# 4_DAC.net
KiCad netlist of a schematic drawn in Altium Designer
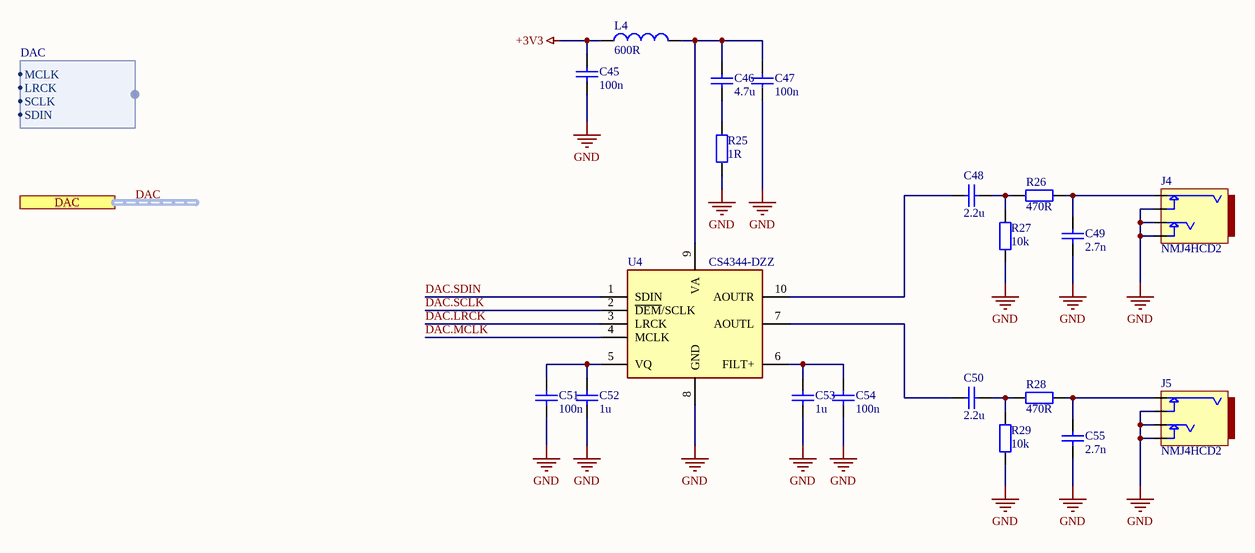
[diagram p0: [4] DAC.SchDoc]

(export (version "E")
  (design (tool "Eeschema 10.0.6"))
  (components
    (comp (ref "C45")
      (value "100n")
      (footprint "STguitar:Capacitor 0603")
      (description "Multilayer Ceramic Capacitors MLCC - SMD/SMT 0603 16VDC 0.1uF 10% X7R")
      (fields
        (field (name "MANUFACTURER PART NUMBER") "EMK107B7104KA-T")
        (field (name "MANUFACTURER") "Taiyo Yuden")
      )
      (libsource (lib "STguitar") (part "Capacitor 100n 10% 0603 EMK107B7104KA-T"))
    )
    (comp (ref "C46")
      (value "4.7u")
      (footprint "STguitar:Capacitor 0603")
      (description "Multilayer Ceramic Capacitors MLCC - SMD/SMT 0603 16VDC 4.7uF 10% X5R")
      (fields
        (field (name "MANUFACTURER PART NUMBER") "EMK107ABJ475KA-T")
        (field (name "MANUFACTURER") "Taiyo Yuden")
      )
      (libsource (lib "STguitar") (part "Capacitor 4.7u 10% 0603 EMK107ABJ475KA-T"))
    )
    (comp (ref "C47")
      (value "100n")
      (footprint "STguitar:Capacitor 0603")
      (description "Multilayer Ceramic Capacitors MLCC - SMD/SMT 0603 16VDC 0.1uF 10% X7R")
      (fields
        (field (name "MANUFACTURER PART NUMBER") "EMK107B7104KA-T")
        (field (name "MANUFACTURER") "Taiyo Yuden")
      )
      (libsource (lib "STguitar") (part "Capacitor 100n 10% 0603 EMK107B7104KA-T"))
    )
    (comp (ref "C48")
      (value "2.2u")
      (footprint "STguitar:Capacitor 0603")
      (description "Multilayer Ceramic Capacitors MLCC - SMD/SMT 0603 16VDC 2.2uF 10% X5R")
      (fields
        (field (name "MANUFACTURER PART NUMBER") "EMK107BJ225KA-T")
        (field (name "MANUFACTURER") "Taiyo Yuden")
      )
      (libsource (lib "STguitar") (part "Capacitor 2.2u 10% 0603 EMK107BJ225KA-T"))
    )
    (comp (ref "C49")
      (value "2.7n")
      (footprint "STguitar:Capacitor 0603")
      (description "Multilayer Ceramic Capacitors MLCC - SMD/SMT 0603 50VDC 2.7nF 10% Low Distort")
      (fields
        (field (name "MANUFACTURER PART NUMBER") "UMK107SD272KA-T")
        (field (name "MANUFACTURER") "Taiyo Yuden")
      )
      (libsource (lib "STguitar") (part "Capacitor 2.7n 10% 0603 UMK107SD272KA-T"))
    )
    (comp (ref "C50")
      (value "2.2u")
      (footprint "STguitar:Capacitor 0603")
      (description "Multilayer Ceramic Capacitors MLCC - SMD/SMT 0603 16VDC 2.2uF 10% X5R")
      (fields
        (field (name "MANUFACTURER PART NUMBER") "EMK107BJ225KA-T")
        (field (name "MANUFACTURER") "Taiyo Yuden")
      )
      (libsource (lib "STguitar") (part "Capacitor 2.2u 10% 0603 EMK107BJ225KA-T"))
    )
    (comp (ref "C51")
      (value "100n")
      (footprint "STguitar:Capacitor 0603")
      (description "Multilayer Ceramic Capacitors MLCC - SMD/SMT 0603 16VDC 0.1uF 10% X7R")
      (fields
        (field (name "MANUFACTURER PART NUMBER") "EMK107B7104KA-T")
        (field (name "MANUFACTURER") "Taiyo Yuden")
      )
      (libsource (lib "STguitar") (part "Capacitor 100n 10% 0603 EMK107B7104KA-T"))
    )
    (comp (ref "C52")
      (value "1u")
      (footprint "STguitar:Capacitor 0603")
      (description "Multilayer Ceramic Capacitors MLCC - SMD/SMT 0603 16VDC 1uF 10% X7R")
      (fields
        (field (name "MANUFACTURER PART NUMBER") "EMK107B7105KA-T")
        (field (name "MANUFACTURER") "Taiyo Yuden")
      )
      (libsource (lib "STguitar") (part "Capacitor 1u 10% 0603 EMK107B7105KA-T"))
    )
    (comp (ref "C53")
      (value "1u")
      (footprint "STguitar:Capacitor 0603")
      (description "Multilayer Ceramic Capacitors MLCC - SMD/SMT 0603 16VDC 1uF 10% X7R")
      (fields
        (field (name "MANUFACTURER PART NUMBER") "EMK107B7105KA-T")
        (field (name "MANUFACTURER") "Taiyo Yuden")
      )
      (libsource (lib "STguitar") (part "Capacitor 1u 10% 0603 EMK107B7105KA-T"))
    )
    (comp (ref "C54")
      (value "100n")
      (footprint "STguitar:Capacitor 0603")
      (description "Multilayer Ceramic Capacitors MLCC - SMD/SMT 0603 16VDC 0.1uF 10% X7R")
      (fields
        (field (name "MANUFACTURER PART NUMBER") "EMK107B7104KA-T")
        (field (name "MANUFACTURER") "Taiyo Yuden")
      )
      (libsource (lib "STguitar") (part "Capacitor 100n 10% 0603 EMK107B7104KA-T"))
    )
    (comp (ref "C55")
      (value "2.7n")
      (footprint "STguitar:Capacitor 0603")
      (description "Multilayer Ceramic Capacitors MLCC - SMD/SMT 0603 50VDC 2.7nF 10% Low Distort")
      (fields
        (field (name "MANUFACTURER PART NUMBER") "UMK107SD272KA-T")
        (field (name "MANUFACTURER") "Taiyo Yuden")
      )
      (libsource (lib "STguitar") (part "Capacitor 2.7n 10% 0603 UMK107SD272KA-T"))
    )
    (comp (ref "J4")
      (value "NMJ4HCD2")
      (footprint "STguitar:Mechanical NMJ4HCD2")
      (description "Phone Connectors 2C MONO 2-SPST NC")
      (fields (field (name "MANUFACTURER") "Neutrik"))
      (libsource (lib "STguitar") (part "Mechanical JACK Phone Connectors 2C MONO 2-SPST NC"))
    )
    (comp (ref "J5")
      (value "NMJ4HCD2")
      (footprint "STguitar:Mechanical NMJ4HCD2")
      (description "Phone Connectors 2C MONO 2-SPST NC")
      (fields (field (name "MANUFACTURER") "Neutrik"))
      (libsource (lib "STguitar") (part "Mechanical JACK Phone Connectors 2C MONO 2-SPST NC"))
    )
    (comp (ref "L4")
      (value "600R")
      (footprint "STguitar:Inductor 0603")
      (description "Ferrite Beads 600ohms 100MHz 300mA Monolithic 0603 SMD")
      (fields
        (field (name "MANUFACTURER PART NUMBER") "HZ0603C601R-10")
        (field (name "MANUFACTURER") "Laird Performance Materials")
      )
      (libsource (lib "STguitar") (part "Inductor 600R 1% 0603 HZ0603C601R-10"))
    )
    (comp (ref "R25")
      (value "1R")
      (footprint "STguitar:Resistor 0603")
      (description "Thin Film Resistors - SMD 1/10W 1 ohm ohm 50 ppm")
      (fields
        (field (name "MANUFACTURER PART NUMBER") "RT0603FRE071RL")
        (field (name "MANUFACTURER") "Yageo")
      )
      (libsource (lib "STguitar") (part "Resistor 1R 1% 0603 RT0603FRE071RL"))
    )
    (comp (ref "R26")
      (value "470R")
      (footprint "STguitar:Resistor 0603")
      (description "Thin Film Resistors - SMD 1/10W 470 ohm 1% 50ppm")
      (fields
        (field (name "MANUFACTURER PART NUMBER") "RT0603FRE07470RL")
        (field (name "MANUFACTURER") "Yageo")
      )
      (libsource (lib "STguitar") (part "Resistor 470R 1% 0603 RT0603FRE07470RL"))
    )
    (comp (ref "R27")
      (value "10k")
      (footprint "STguitar:Resistor 0603")
      (description "Thin Film Resistors - SMD 10K ohm 1% 1/10W")
      (fields
        (field (name "MANUFACTURER PART NUMBER") "RT0603FRE0710KL")
        (field (name "MANUFACTURER") "Yageo")
      )
      (libsource (lib "STguitar") (part "Resistor 10k 1% 0603 RT0603FRE0710KL"))
    )
    (comp (ref "R28")
      (value "470R")
      (footprint "STguitar:Resistor 0603")
      (description "Thin Film Resistors - SMD 1/10W 470 ohm 1% 50ppm")
      (fields
        (field (name "MANUFACTURER PART NUMBER") "RT0603FRE07470RL")
        (field (name "MANUFACTURER") "Yageo")
      )
      (libsource (lib "STguitar") (part "Resistor 470R 1% 0603 RT0603FRE07470RL"))
    )
    (comp (ref "R29")
      (value "10k")
      (footprint "STguitar:Resistor 0603")
      (description "Thin Film Resistors - SMD 10K ohm 1% 1/10W")
      (fields
        (field (name "MANUFACTURER PART NUMBER") "RT0603FRE0710KL")
        (field (name "MANUFACTURER") "Yageo")
      )
      (libsource (lib "STguitar") (part "Resistor 10k 1% 0603 RT0603FRE0710KL"))
    )
    (comp (ref "U4")
      (value "CS4344-DZZ")
      (footprint "STguitar:TSSOP10")
      (description "Audio D/A Converter ICs Stereo DAC 24-Bit 192kHz")
      (fields (field (name "MANUFACTURER") "Cirrus Logic"))
      (libsource (lib "STguitar") (part "IC Audio D/A Converter ICs Stereo DAC 24-Bit 192kHz CS4344-DZZ"))
    )
  )
  (nets
    (net (code "2") (name "+3V3") (class "Default")
      (node (ref "C45") (pin "2") (pinfunction "2_2") (pintype "passive"))
      (node (ref "L4") (pin "1") (pinfunction "1_1") (pintype "passive"))
    )
    (net (code "3") (name "/DAC.LRCK") (class "Default")
      (node (ref "U4") (pin "3") (pinfunction "LRCK_3") (pintype "passive"))
    )
    (net (code "4") (name "/DAC.MCLK") (class "Default")
      (node (ref "U4") (pin "4") (pinfunction "MCLK_4") (pintype "passive"))
    )
    (net (code "5") (name "/DAC.SCLK") (class "Default")
      (node (ref "U4") (pin "2") (pinfunction "~{DEM}/SCLK_2") (pintype "passive"))
    )
    (net (code "6") (name "/DAC.SDIN") (class "Default")
      (node (ref "U4") (pin "1") (pinfunction "SDIN_1") (pintype "passive"))
    )
    (net (code "8") (name "GND") (class "Default")
      (node (ref "C45") (pin "1") (pinfunction "1_1") (pintype "passive"))
      (node (ref "C47") (pin "1") (pinfunction "1_1") (pintype "passive"))
      (node (ref "C49") (pin "1") (pinfunction "1_1") (pintype "passive"))
      (node (ref "C51") (pin "1") (pinfunction "1_1") (pintype "passive"))
      (node (ref "C52") (pin "1") (pinfunction "1_1") (pintype "passive"))
      (node (ref "C53") (pin "1") (pinfunction "1_1") (pintype "passive"))
      (node (ref "C54") (pin "1") (pinfunction "1_1") (pintype "passive"))
      (node (ref "C55") (pin "1") (pinfunction "1_1") (pintype "passive"))
      (node (ref "J4") (pin "1") (pinfunction "S_1") (pintype "passive"))
      (node (ref "J4") (pin "2") (pinfunction "SN_2") (pintype "passive"))
      (node (ref "J4") (pin "4") (pinfunction "TN_4") (pintype "passive"))
      (node (ref "J5") (pin "1") (pinfunction "S_1") (pintype "passive"))
      (node (ref "J5") (pin "2") (pinfunction "SN_2") (pintype "passive"))
      (node (ref "J5") (pin "4") (pinfunction "TN_4") (pintype "passive"))
      (node (ref "R25") (pin "1") (pinfunction "1_1") (pintype "passive"))
      (node (ref "R27") (pin "1") (pinfunction "1_1") (pintype "passive"))
      (node (ref "R29") (pin "1") (pinfunction "1_1") (pintype "passive"))
      (node (ref "U4") (pin "8") (pinfunction "GND_8") (pintype "passive"))
    )
    (net (code "9") (name "Net-(C46-Pad1)") (class "Default")
      (node (ref "C46") (pin "1") (pinfunction "1_1") (pintype "passive"))
      (node (ref "R25") (pin "2") (pinfunction "2_2") (pintype "passive"))
    )
    (net (code "10") (name "Net-(C48-Pad2)") (class "Default")
      (node (ref "C48") (pin "2") (pinfunction "2_2") (pintype "passive"))
      (node (ref "R26") (pin "1") (pinfunction "1_1") (pintype "passive"))
      (node (ref "R27") (pin "2") (pinfunction "2_2") (pintype "passive"))
    )
    (net (code "11") (name "Net-(C50-Pad2)") (class "Default")
      (node (ref "C50") (pin "2") (pinfunction "2_2") (pintype "passive"))
      (node (ref "R28") (pin "1") (pinfunction "1_1") (pintype "passive"))
      (node (ref "R29") (pin "2") (pinfunction "2_2") (pintype "passive"))
    )
    (net (code "12") (name "Net-(J4-T)") (class "Default")
      (node (ref "C49") (pin "2") (pinfunction "2_2") (pintype "passive"))
      (node (ref "J4") (pin "3") (pinfunction "T_3") (pintype "passive"))
      (node (ref "R26") (pin "2") (pinfunction "2_2") (pintype "passive"))
    )
    (net (code "13") (name "Net-(J5-T)") (class "Default")
      (node (ref "C55") (pin "2") (pinfunction "2_2") (pintype "passive"))
      (node (ref "J5") (pin "3") (pinfunction "T_3") (pintype "passive"))
      (node (ref "R28") (pin "2") (pinfunction "2_2") (pintype "passive"))
    )
    (net (code "14") (name "Net-(U4-AOUTL)") (class "Default")
      (node (ref "C50") (pin "1") (pinfunction "1_1") (pintype "passive"))
      (node (ref "U4") (pin "7") (pinfunction "AOUTL_7") (pintype "passive"))
    )
    (net (code "15") (name "Net-(U4-AOUTR)") (class "Default")
      (node (ref "C48") (pin "1") (pinfunction "1_1") (pintype "passive"))
      (node (ref "U4") (pin "10") (pinfunction "AOUTR_10") (pintype "passive"))
    )
    (net (code "16") (name "Net-(U4-FILT+)") (class "Default")
      (node (ref "C53") (pin "2") (pinfunction "2_2") (pintype "passive"))
      (node (ref "C54") (pin "2") (pinfunction "2_2") (pintype "passive"))
      (node (ref "U4") (pin "6") (pinfunction "FILT+_6") (pintype "passive"))
    )
    (net (code "17") (name "Net-(U4-VA)") (class "Default")
      (node (ref "C46") (pin "2") (pinfunction "2_2") (pintype "passive"))
      (node (ref "C47") (pin "2") (pinfunction "2_2") (pintype "passive"))
      (node (ref "L4") (pin "2") (pinfunction "2_2") (pintype "passive"))
      (node (ref "U4") (pin "9") (pinfunction "VA_9") (pintype "passive"))
    )
    (net (code "18") (name "Net-(U4-VQ)") (class "Default")
      (node (ref "C51") (pin "2") (pinfunction "2_2") (pintype "passive"))
      (node (ref "C52") (pin "2") (pinfunction "2_2") (pintype "passive"))
      (node (ref "U4") (pin "5") (pinfunction "VQ_5") (pintype "passive"))
    )
  )
)
